# SH6_-_SCIENCECONTROLS.net
KiCad netlist of a schematic drawn in Altium Designer
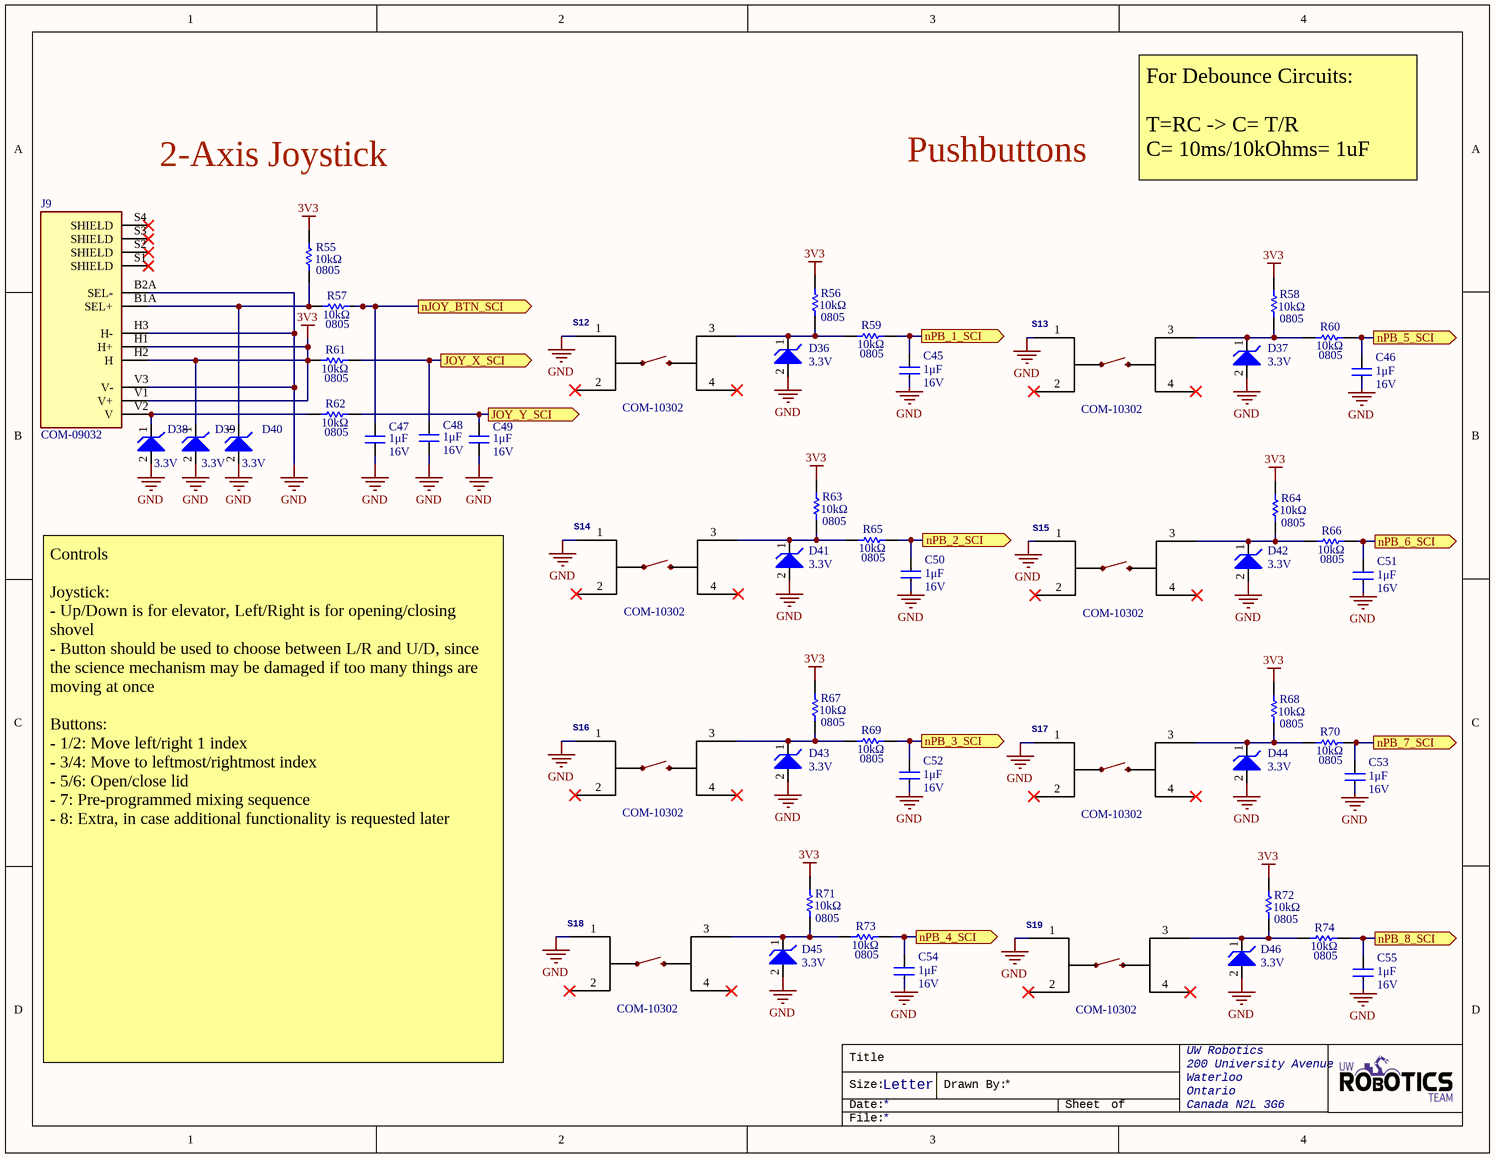
[diagram p0: SH6 - SCIENCECONTROLS.SchDoc]

(export (version "E")
  (design (tool "Eeschema 10.0.6"))
  (components
    (comp (ref "C45")
      (value "1μF")
      (footprint "CAP2012")
      (description "CAP CER 1UF 16V X7R 0805")
      (fields
        (field (name "TOLERANCE") "10%")
        (field (name "VOLTAGE RATING") "16V")
        (field (name "Comment") "CAP_1uF_16V_0805")
      )
      (libsource (lib "UWRT_Schematic_Library_2020") (part "CAP_1uF_16V_0805"))
    )
    (comp (ref "C46")
      (value "1μF")
      (footprint "CAP2012")
      (description "CAP CER 1UF 16V X7R 0805")
      (fields
        (field (name "TOLERANCE") "10%")
        (field (name "VOLTAGE RATING") "16V")
        (field (name "Comment") "CAP_1uF_16V_0805")
      )
      (libsource (lib "UWRT_Schematic_Library_2020") (part "CAP_1uF_16V_0805"))
    )
    (comp (ref "C47")
      (value "1μF")
      (footprint "CAP2012")
      (description "CAP CER 1UF 16V X7R 0805")
      (fields
        (field (name "TOLERANCE") "10%")
        (field (name "VOLTAGE RATING") "16V")
        (field (name "Comment") "CAP_1uF_16V_0805")
      )
      (libsource (lib "UWRT_Schematic_Library_2020") (part "CAP_1uF_16V_0805"))
    )
    (comp (ref "C48")
      (value "1μF")
      (footprint "CAP2012")
      (description "CAP CER 1UF 16V X7R 0805")
      (fields
        (field (name "TOLERANCE") "10%")
        (field (name "VOLTAGE RATING") "16V")
        (field (name "Comment") "CAP_1uF_16V_0805")
      )
      (libsource (lib "UWRT_Schematic_Library_2020") (part "CAP_1uF_16V_0805"))
    )
    (comp (ref "C49")
      (value "1μF")
      (footprint "CAP2012")
      (description "CAP CER 1UF 16V X7R 0805")
      (fields
        (field (name "TOLERANCE") "10%")
        (field (name "VOLTAGE RATING") "16V")
        (field (name "Comment") "CAP_1uF_16V_0805")
      )
      (libsource (lib "UWRT_Schematic_Library_2020") (part "CAP_1uF_16V_0805"))
    )
    (comp (ref "C50")
      (value "1μF")
      (footprint "CAP2012")
      (description "CAP CER 1UF 16V X7R 0805")
      (fields
        (field (name "TOLERANCE") "10%")
        (field (name "VOLTAGE RATING") "16V")
        (field (name "Comment") "CAP_1uF_16V_0805")
      )
      (libsource (lib "UWRT_Schematic_Library_2020") (part "CAP_1uF_16V_0805"))
    )
    (comp (ref "C51")
      (value "1μF")
      (footprint "CAP2012")
      (description "CAP CER 1UF 16V X7R 0805")
      (fields
        (field (name "TOLERANCE") "10%")
        (field (name "VOLTAGE RATING") "16V")
        (field (name "Comment") "CAP_1uF_16V_0805")
      )
      (libsource (lib "UWRT_Schematic_Library_2020") (part "CAP_1uF_16V_0805"))
    )
    (comp (ref "C52")
      (value "1μF")
      (footprint "CAP2012")
      (description "CAP CER 1UF 16V X7R 0805")
      (fields
        (field (name "TOLERANCE") "10%")
        (field (name "VOLTAGE RATING") "16V")
        (field (name "Comment") "CAP_1uF_16V_0805")
      )
      (libsource (lib "UWRT_Schematic_Library_2020") (part "CAP_1uF_16V_0805"))
    )
    (comp (ref "C53")
      (value "1μF")
      (footprint "CAP2012")
      (description "CAP CER 1UF 16V X7R 0805")
      (fields
        (field (name "TOLERANCE") "10%")
        (field (name "VOLTAGE RATING") "16V")
        (field (name "Comment") "CAP_1uF_16V_0805")
      )
      (libsource (lib "UWRT_Schematic_Library_2020") (part "CAP_1uF_16V_0805"))
    )
    (comp (ref "C54")
      (value "1μF")
      (footprint "CAP2012")
      (description "CAP CER 1UF 16V X7R 0805")
      (fields
        (field (name "TOLERANCE") "10%")
        (field (name "VOLTAGE RATING") "16V")
        (field (name "Comment") "CAP_1uF_16V_0805")
      )
      (libsource (lib "UWRT_Schematic_Library_2020") (part "CAP_1uF_16V_0805"))
    )
    (comp (ref "C55")
      (value "1μF")
      (footprint "CAP2012")
      (description "CAP CER 1UF 16V X7R 0805")
      (fields
        (field (name "TOLERANCE") "10%")
        (field (name "VOLTAGE RATING") "16V")
        (field (name "Comment") "CAP_1uF_16V_0805")
      )
      (libsource (lib "UWRT_Schematic_Library_2020") (part "CAP_1uF_16V_0805"))
    )
    (comp (ref "D36")
      (value "TVS_DIODE_UNIDIR_3.3V")
      (footprint "SOD523")
      (description "TVS DIODE 3.3V 14.1V SOD523. Used to protect each connector input line going into the MCU.")
      (fields (field (name "REVERSE STANDOFF VOLTAGE") "3.3V"))
      (libsource (lib "UWRT_Schematic_Library_2020") (part "TVS_DIODE_UNIDIR_3.3V"))
    )
    (comp (ref "D37")
      (value "TVS_DIODE_UNIDIR_3.3V")
      (footprint "SOD523")
      (description "TVS DIODE 3.3V 14.1V SOD523. Used to protect each connector input line going into the MCU.")
      (fields (field (name "REVERSE STANDOFF VOLTAGE") "3.3V"))
      (libsource (lib "UWRT_Schematic_Library_2020") (part "TVS_DIODE_UNIDIR_3.3V"))
    )
    (comp (ref "D38")
      (value "TVS_DIODE_UNIDIR_3.3V")
      (footprint "SOD523")
      (description "TVS DIODE 3.3V 14.1V SOD523. Used to protect each connector input line going into the MCU.")
      (fields (field (name "REVERSE STANDOFF VOLTAGE") "3.3V"))
      (libsource (lib "UWRT_Schematic_Library_2020") (part "TVS_DIODE_UNIDIR_3.3V"))
    )
    (comp (ref "D39")
      (value "TVS_DIODE_UNIDIR_3.3V")
      (footprint "SOD523")
      (description "TVS DIODE 3.3V 14.1V SOD523. Used to protect each connector input line going into the MCU.")
      (fields (field (name "REVERSE STANDOFF VOLTAGE") "3.3V"))
      (libsource (lib "UWRT_Schematic_Library_2020") (part "TVS_DIODE_UNIDIR_3.3V"))
    )
    (comp (ref "D40")
      (value "TVS_DIODE_UNIDIR_3.3V")
      (footprint "SOD523")
      (description "TVS DIODE 3.3V 14.1V SOD523. Used to protect each connector input line going into the MCU.")
      (fields (field (name "REVERSE STANDOFF VOLTAGE") "3.3V"))
      (libsource (lib "UWRT_Schematic_Library_2020") (part "TVS_DIODE_UNIDIR_3.3V"))
    )
    (comp (ref "D41")
      (value "TVS_DIODE_UNIDIR_3.3V")
      (footprint "SOD523")
      (description "TVS DIODE 3.3V 14.1V SOD523. Used to protect each connector input line going into the MCU.")
      (fields (field (name "REVERSE STANDOFF VOLTAGE") "3.3V"))
      (libsource (lib "UWRT_Schematic_Library_2020") (part "TVS_DIODE_UNIDIR_3.3V"))
    )
    (comp (ref "D42")
      (value "TVS_DIODE_UNIDIR_3.3V")
      (footprint "SOD523")
      (description "TVS DIODE 3.3V 14.1V SOD523. Used to protect each connector input line going into the MCU.")
      (fields (field (name "REVERSE STANDOFF VOLTAGE") "3.3V"))
      (libsource (lib "UWRT_Schematic_Library_2020") (part "TVS_DIODE_UNIDIR_3.3V"))
    )
    (comp (ref "D43")
      (value "TVS_DIODE_UNIDIR_3.3V")
      (footprint "SOD523")
      (description "TVS DIODE 3.3V 14.1V SOD523. Used to protect each connector input line going into the MCU.")
      (fields (field (name "REVERSE STANDOFF VOLTAGE") "3.3V"))
      (libsource (lib "UWRT_Schematic_Library_2020") (part "TVS_DIODE_UNIDIR_3.3V"))
    )
    (comp (ref "D44")
      (value "TVS_DIODE_UNIDIR_3.3V")
      (footprint "SOD523")
      (description "TVS DIODE 3.3V 14.1V SOD523. Used to protect each connector input line going into the MCU.")
      (fields (field (name "REVERSE STANDOFF VOLTAGE") "3.3V"))
      (libsource (lib "UWRT_Schematic_Library_2020") (part "TVS_DIODE_UNIDIR_3.3V"))
    )
    (comp (ref "D45")
      (value "TVS_DIODE_UNIDIR_3.3V")
      (footprint "SOD523")
      (description "TVS DIODE 3.3V 14.1V SOD523. Used to protect each connector input line going into the MCU.")
      (fields (field (name "REVERSE STANDOFF VOLTAGE") "3.3V"))
      (libsource (lib "UWRT_Schematic_Library_2020") (part "TVS_DIODE_UNIDIR_3.3V"))
    )
    (comp (ref "D46")
      (value "TVS_DIODE_UNIDIR_3.3V")
      (footprint "SOD523")
      (description "TVS DIODE 3.3V 14.1V SOD523. Used to protect each connector input line going into the MCU.")
      (fields (field (name "REVERSE STANDOFF VOLTAGE") "3.3V"))
      (libsource (lib "UWRT_Schematic_Library_2020") (part "TVS_DIODE_UNIDIR_3.3V"))
    )
    (comp (ref "J9")
      (value "2_AXIS_JOYSTICK")
      (footprint "2_AXIS_JOYSTICK")
      (description "JOYSTICK 10K OHM 2 AXIS TH")
      (fields (field (name "MANUFACTURER PART NUMBER 1") "COM-09032"))
      (libsource (lib "UWRT_Schematic_Library_2020") (part "2_AXIS_JOYSTICK"))
    )
    (comp (ref "R55")
      (value "10kΩ")
      (footprint "RESC0805")
      (description "RES 10K OHM 5% 1/8W 0805")
      (fields (field (name "CASE CODE (IMPERIAL)") "0805") (field (name "Comment") "RES_10kΩ_0805_5%"))
      (libsource (lib "UWRT_Schematic_Library_2020") (part "RES_10kΩ_0805_5%"))
    )
    (comp (ref "R56")
      (value "10kΩ")
      (footprint "RESC0805")
      (description "RES 10K OHM 5% 1/8W 0805")
      (fields (field (name "CASE CODE (IMPERIAL)") "0805") (field (name "Comment") "RES_10kΩ_0805_5%"))
      (libsource (lib "UWRT_Schematic_Library_2020") (part "RES_10kΩ_0805_5%"))
    )
    (comp (ref "R57")
      (value "10kΩ")
      (footprint "RESC0805")
      (description "RES 10K OHM 5% 1/8W 0805")
      (fields (field (name "CASE CODE (IMPERIAL)") "0805") (field (name "Comment") "RES_10kΩ_0805_5%"))
      (libsource (lib "UWRT_Schematic_Library_2020") (part "RES_10kΩ_0805_5%"))
    )
    (comp (ref "R58")
      (value "10kΩ")
      (footprint "RESC0805")
      (description "RES 10K OHM 5% 1/8W 0805")
      (fields (field (name "CASE CODE (IMPERIAL)") "0805") (field (name "Comment") "RES_10kΩ_0805_5%"))
      (libsource (lib "UWRT_Schematic_Library_2020") (part "RES_10kΩ_0805_5%"))
    )
    (comp (ref "R59")
      (value "10kΩ")
      (footprint "RESC0805")
      (description "RES 10K OHM 5% 1/8W 0805")
      (fields (field (name "CASE CODE (IMPERIAL)") "0805") (field (name "Comment") "RES_10kΩ_0805_5%"))
      (libsource (lib "UWRT_Schematic_Library_2020") (part "RES_10kΩ_0805_5%"))
    )
    (comp (ref "R60")
      (value "10kΩ")
      (footprint "RESC0805")
      (description "RES 10K OHM 5% 1/8W 0805")
      (fields (field (name "CASE CODE (IMPERIAL)") "0805") (field (name "Comment") "RES_10kΩ_0805_5%"))
      (libsource (lib "UWRT_Schematic_Library_2020") (part "RES_10kΩ_0805_5%"))
    )
    (comp (ref "R61")
      (value "10kΩ")
      (footprint "RESC0805")
      (description "RES 10K OHM 5% 1/8W 0805")
      (fields (field (name "CASE CODE (IMPERIAL)") "0805") (field (name "Comment") "RES_10kΩ_0805_5%"))
      (libsource (lib "UWRT_Schematic_Library_2020") (part "RES_10kΩ_0805_5%"))
    )
    (comp (ref "R62")
      (value "10kΩ")
      (footprint "RESC0805")
      (description "RES 10K OHM 5% 1/8W 0805")
      (fields (field (name "CASE CODE (IMPERIAL)") "0805") (field (name "Comment") "RES_10kΩ_0805_5%"))
      (libsource (lib "UWRT_Schematic_Library_2020") (part "RES_10kΩ_0805_5%"))
    )
    (comp (ref "R63")
      (value "10kΩ")
      (footprint "RESC0805")
      (description "RES 10K OHM 5% 1/8W 0805")
      (fields (field (name "CASE CODE (IMPERIAL)") "0805") (field (name "Comment") "RES_10kΩ_0805_5%"))
      (libsource (lib "UWRT_Schematic_Library_2020") (part "RES_10kΩ_0805_5%"))
    )
    (comp (ref "R64")
      (value "10kΩ")
      (footprint "RESC0805")
      (description "RES 10K OHM 5% 1/8W 0805")
      (fields (field (name "CASE CODE (IMPERIAL)") "0805") (field (name "Comment") "RES_10kΩ_0805_5%"))
      (libsource (lib "UWRT_Schematic_Library_2020") (part "RES_10kΩ_0805_5%"))
    )
    (comp (ref "R65")
      (value "10kΩ")
      (footprint "RESC0805")
      (description "RES 10K OHM 5% 1/8W 0805")
      (fields (field (name "CASE CODE (IMPERIAL)") "0805") (field (name "Comment") "RES_10kΩ_0805_5%"))
      (libsource (lib "UWRT_Schematic_Library_2020") (part "RES_10kΩ_0805_5%"))
    )
    (comp (ref "R66")
      (value "10kΩ")
      (footprint "RESC0805")
      (description "RES 10K OHM 5% 1/8W 0805")
      (fields (field (name "CASE CODE (IMPERIAL)") "0805") (field (name "Comment") "RES_10kΩ_0805_5%"))
      (libsource (lib "UWRT_Schematic_Library_2020") (part "RES_10kΩ_0805_5%"))
    )
    (comp (ref "R67")
      (value "10kΩ")
      (footprint "RESC0805")
      (description "RES 10K OHM 5% 1/8W 0805")
      (fields (field (name "CASE CODE (IMPERIAL)") "0805") (field (name "Comment") "RES_10kΩ_0805_5%"))
      (libsource (lib "UWRT_Schematic_Library_2020") (part "RES_10kΩ_0805_5%"))
    )
    (comp (ref "R68")
      (value "10kΩ")
      (footprint "RESC0805")
      (description "RES 10K OHM 5% 1/8W 0805")
      (fields (field (name "CASE CODE (IMPERIAL)") "0805") (field (name "Comment") "RES_10kΩ_0805_5%"))
      (libsource (lib "UWRT_Schematic_Library_2020") (part "RES_10kΩ_0805_5%"))
    )
    (comp (ref "R69")
      (value "10kΩ")
      (footprint "RESC0805")
      (description "RES 10K OHM 5% 1/8W 0805")
      (fields (field (name "CASE CODE (IMPERIAL)") "0805") (field (name "Comment") "RES_10kΩ_0805_5%"))
      (libsource (lib "UWRT_Schematic_Library_2020") (part "RES_10kΩ_0805_5%"))
    )
    (comp (ref "R70")
      (value "10kΩ")
      (footprint "RESC0805")
      (description "RES 10K OHM 5% 1/8W 0805")
      (fields (field (name "CASE CODE (IMPERIAL)") "0805") (field (name "Comment") "RES_10kΩ_0805_5%"))
      (libsource (lib "UWRT_Schematic_Library_2020") (part "RES_10kΩ_0805_5%"))
    )
    (comp (ref "R71")
      (value "10kΩ")
      (footprint "RESC0805")
      (description "RES 10K OHM 5% 1/8W 0805")
      (fields (field (name "CASE CODE (IMPERIAL)") "0805") (field (name "Comment") "RES_10kΩ_0805_5%"))
      (libsource (lib "UWRT_Schematic_Library_2020") (part "RES_10kΩ_0805_5%"))
    )
    (comp (ref "R72")
      (value "10kΩ")
      (footprint "RESC0805")
      (description "RES 10K OHM 5% 1/8W 0805")
      (fields (field (name "CASE CODE (IMPERIAL)") "0805") (field (name "Comment") "RES_10kΩ_0805_5%"))
      (libsource (lib "UWRT_Schematic_Library_2020") (part "RES_10kΩ_0805_5%"))
    )
    (comp (ref "R73")
      (value "10kΩ")
      (footprint "RESC0805")
      (description "RES 10K OHM 5% 1/8W 0805")
      (fields (field (name "CASE CODE (IMPERIAL)") "0805") (field (name "Comment") "RES_10kΩ_0805_5%"))
      (libsource (lib "UWRT_Schematic_Library_2020") (part "RES_10kΩ_0805_5%"))
    )
    (comp (ref "R74")
      (value "10kΩ")
      (footprint "RESC0805")
      (description "RES 10K OHM 5% 1/8W 0805")
      (fields (field (name "CASE CODE (IMPERIAL)") "0805") (field (name "Comment") "RES_10kΩ_0805_5%"))
      (libsource (lib "UWRT_Schematic_Library_2020") (part "RES_10kΩ_0805_5%"))
    )
    (comp (ref "S12")
      (value "Pushbutton")
      (footprint "TACTILE_SWITCH_PTH_12MM")
      (description "TACTILE MOMENTARY PUSHBUTTON SPST")
      (fields (field (name "MANUFACTURER PART NUMBER 1") "COM-10302"))
      (libsource (lib "UWRT_Schematic_Library_2020") (part "MOMENTARY_SWITCH_TH"))
    )
    (comp (ref "S13")
      (value "Pushbutton")
      (footprint "TACTILE_SWITCH_PTH_12MM")
      (description "TACTILE MOMENTARY PUSHBUTTON SPST")
      (fields (field (name "MANUFACTURER PART NUMBER 1") "COM-10302"))
      (libsource (lib "UWRT_Schematic_Library_2020") (part "MOMENTARY_SWITCH_TH"))
    )
    (comp (ref "S14")
      (value "Pushbutton")
      (footprint "TACTILE_SWITCH_PTH_12MM")
      (description "TACTILE MOMENTARY PUSHBUTTON SPST")
      (fields (field (name "MANUFACTURER PART NUMBER 1") "COM-10302"))
      (libsource (lib "UWRT_Schematic_Library_2020") (part "MOMENTARY_SWITCH_TH"))
    )
    (comp (ref "S15")
      (value "Pushbutton")
      (footprint "TACTILE_SWITCH_PTH_12MM")
      (description "TACTILE MOMENTARY PUSHBUTTON SPST")
      (fields (field (name "MANUFACTURER PART NUMBER 1") "COM-10302"))
      (libsource (lib "UWRT_Schematic_Library_2020") (part "MOMENTARY_SWITCH_TH"))
    )
    (comp (ref "S16")
      (value "Pushbutton")
      (footprint "TACTILE_SWITCH_PTH_12MM")
      (description "TACTILE MOMENTARY PUSHBUTTON SPST")
      (fields (field (name "MANUFACTURER PART NUMBER 1") "COM-10302"))
      (libsource (lib "UWRT_Schematic_Library_2020") (part "MOMENTARY_SWITCH_TH"))
    )
    (comp (ref "S17")
      (value "Pushbutton")
      (footprint "TACTILE_SWITCH_PTH_12MM")
      (description "TACTILE MOMENTARY PUSHBUTTON SPST")
      (fields (field (name "MANUFACTURER PART NUMBER 1") "COM-10302"))
      (libsource (lib "UWRT_Schematic_Library_2020") (part "MOMENTARY_SWITCH_TH"))
    )
    (comp (ref "S18")
      (value "Pushbutton")
      (footprint "TACTILE_SWITCH_PTH_12MM")
      (description "TACTILE MOMENTARY PUSHBUTTON SPST")
      (fields (field (name "MANUFACTURER PART NUMBER 1") "COM-10302"))
      (libsource (lib "UWRT_Schematic_Library_2020") (part "MOMENTARY_SWITCH_TH"))
    )
    (comp (ref "S19")
      (value "Pushbutton")
      (footprint "TACTILE_SWITCH_PTH_12MM")
      (description "TACTILE MOMENTARY PUSHBUTTON SPST")
      (fields (field (name "MANUFACTURER PART NUMBER 1") "COM-10302"))
      (libsource (lib "UWRT_Schematic_Library_2020") (part "MOMENTARY_SWITCH_TH"))
    )
  )
  (nets
    (net (code "1") (name "/JOY_X_SCI") (class "Default")
      (node (ref "C48") (pin "2") (pinfunction "2_2") (pintype "passive"))
      (node (ref "R61") (pin "2") (pinfunction "2_2") (pintype "passive"))
    )
    (net (code "2") (name "/JOY_Y_SCI") (class "Default")
      (node (ref "C49") (pin "2") (pinfunction "2_2") (pintype "passive"))
      (node (ref "R62") (pin "2") (pinfunction "2_2") (pintype "passive"))
    )
    (net (code "3") (name "/nJOY_BTN_SCI") (class "Default")
      (node (ref "C47") (pin "2") (pinfunction "2_2") (pintype "passive"))
      (node (ref "R57") (pin "2") (pinfunction "2_2") (pintype "passive"))
    )
    (net (code "4") (name "/nPB_1_SCI") (class "Default")
      (node (ref "C45") (pin "2") (pinfunction "2_2") (pintype "passive"))
      (node (ref "R59") (pin "2") (pinfunction "2_2") (pintype "passive"))
    )
    (net (code "5") (name "/nPB_2_SCI") (class "Default")
      (node (ref "C50") (pin "2") (pinfunction "2_2") (pintype "passive"))
      (node (ref "R65") (pin "2") (pinfunction "2_2") (pintype "passive"))
    )
    (net (code "6") (name "/nPB_3_SCI") (class "Default")
      (node (ref "C52") (pin "2") (pinfunction "2_2") (pintype "passive"))
      (node (ref "R69") (pin "2") (pinfunction "2_2") (pintype "passive"))
    )
    (net (code "7") (name "/nPB_4_SCI") (class "Default")
      (node (ref "C54") (pin "2") (pinfunction "2_2") (pintype "passive"))
      (node (ref "R73") (pin "2") (pinfunction "2_2") (pintype "passive"))
    )
    (net (code "8") (name "/nPB_5_SCI") (class "Default")
      (node (ref "C46") (pin "2") (pinfunction "2_2") (pintype "passive"))
      (node (ref "R60") (pin "2") (pinfunction "2_2") (pintype "passive"))
    )
    (net (code "9") (name "/nPB_6_SCI") (class "Default")
      (node (ref "C51") (pin "2") (pinfunction "2_2") (pintype "passive"))
      (node (ref "R66") (pin "2") (pinfunction "2_2") (pintype "passive"))
    )
    (net (code "10") (name "/nPB_7_SCI") (class "Default")
      (node (ref "C53") (pin "2") (pinfunction "2_2") (pintype "passive"))
      (node (ref "R70") (pin "2") (pinfunction "2_2") (pintype "passive"))
    )
    (net (code "11") (name "/nPB_8_SCI") (class "Default")
      (node (ref "C55") (pin "2") (pinfunction "2_2") (pintype "passive"))
      (node (ref "R74") (pin "2") (pinfunction "2_2") (pintype "passive"))
    )
    (net (code "12") (name "3V3") (class "Default")
      (node (ref "D39") (pin "1") (pinfunction "1_1") (pintype "passive"))
      (node (ref "J9") (pin "H1") (pinfunction "H+_H1") (pintype "passive"))
      (node (ref "J9") (pin "H2") (pinfunction "H_H2") (pintype "passive"))
      (node (ref "J9") (pin "V1") (pinfunction "V+_V1") (pintype "passive"))
      (node (ref "R55") (pin "1") (pinfunction "1_1") (pintype "passive"))
      (node (ref "R56") (pin "1") (pinfunction "1_1") (pintype "passive"))
      (node (ref "R58") (pin "1") (pinfunction "1_1") (pintype "passive"))
      (node (ref "R61") (pin "1") (pinfunction "1_1") (pintype "passive"))
      (node (ref "R63") (pin "1") (pinfunction "1_1") (pintype "passive"))
      (node (ref "R64") (pin "1") (pinfunction "1_1") (pintype "passive"))
      (node (ref "R67") (pin "1") (pinfunction "1_1") (pintype "passive"))
      (node (ref "R68") (pin "1") (pinfunction "1_1") (pintype "passive"))
      (node (ref "R71") (pin "1") (pinfunction "1_1") (pintype "passive"))
      (node (ref "R72") (pin "1") (pinfunction "1_1") (pintype "passive"))
    )
    (net (code "13") (name "GND") (class "Default")
      (node (ref "C45") (pin "1") (pinfunction "1_1") (pintype "passive"))
      (node (ref "C46") (pin "1") (pinfunction "1_1") (pintype "passive"))
      (node (ref "C47") (pin "1") (pinfunction "1_1") (pintype "passive"))
      (node (ref "C48") (pin "1") (pinfunction "1_1") (pintype "passive"))
      (node (ref "C49") (pin "1") (pinfunction "1_1") (pintype "passive"))
      (node (ref "C50") (pin "1") (pinfunction "1_1") (pintype "passive"))
      (node (ref "C51") (pin "1") (pinfunction "1_1") (pintype "passive"))
      (node (ref "C52") (pin "1") (pinfunction "1_1") (pintype "passive"))
      (node (ref "C53") (pin "1") (pinfunction "1_1") (pintype "passive"))
      (node (ref "C54") (pin "1") (pinfunction "1_1") (pintype "passive"))
      (node (ref "C55") (pin "1") (pinfunction "1_1") (pintype "passive"))
      (node (ref "D36") (pin "2") (pinfunction "2_2") (pintype "passive"))
      (node (ref "D37") (pin "2") (pinfunction "2_2") (pintype "passive"))
      (node (ref "D38") (pin "2") (pinfunction "2_2") (pintype "passive"))
      (node (ref "D39") (pin "2") (pinfunction "2_2") (pintype "passive"))
      (node (ref "D40") (pin "2") (pinfunction "2_2") (pintype "passive"))
      (node (ref "D41") (pin "2") (pinfunction "2_2") (pintype "passive"))
      (node (ref "D42") (pin "2") (pinfunction "2_2") (pintype "passive"))
      (node (ref "D43") (pin "2") (pinfunction "2_2") (pintype "passive"))
      (node (ref "D44") (pin "2") (pinfunction "2_2") (pintype "passive"))
      (node (ref "D45") (pin "2") (pinfunction "2_2") (pintype "passive"))
      (node (ref "D46") (pin "2") (pinfunction "2_2") (pintype "passive"))
      (node (ref "J9") (pin "B2A") (pinfunction "SEL-_B2A") (pintype "passive"))
      (node (ref "J9") (pin "H3") (pinfunction "H-_H3") (pintype "passive"))
      (node (ref "J9") (pin "V3") (pinfunction "V-_V3") (pintype "passive"))
      (node (ref "S12") (pin "1") (pinfunction "1_1") (pintype "passive"))
      (node (ref "S13") (pin "1") (pinfunction "1_1") (pintype "passive"))
      (node (ref "S14") (pin "1") (pinfunction "1_1") (pintype "passive"))
      (node (ref "S15") (pin "1") (pinfunction "1_1") (pintype "passive"))
      (node (ref "S16") (pin "1") (pinfunction "1_1") (pintype "passive"))
      (node (ref "S17") (pin "1") (pinfunction "1_1") (pintype "passive"))
      (node (ref "S18") (pin "1") (pinfunction "1_1") (pintype "passive"))
      (node (ref "S19") (pin "1") (pinfunction "1_1") (pintype "passive"))
    )
    (net (code "14") (name "Net-(D36-Pad1)") (class "Default")
      (node (ref "D36") (pin "1") (pinfunction "1_1") (pintype "passive"))
      (node (ref "R56") (pin "2") (pinfunction "2_2") (pintype "passive"))
      (node (ref "R59") (pin "1") (pinfunction "1_1") (pintype "passive"))
      (node (ref "S12") (pin "3") (pinfunction "3_3") (pintype "passive"))
    )
    (net (code "15") (name "Net-(D37-Pad1)") (class "Default")
      (node (ref "D37") (pin "1") (pinfunction "1_1") (pintype "passive"))
      (node (ref "R58") (pin "2") (pinfunction "2_2") (pintype "passive"))
      (node (ref "R60") (pin "1") (pinfunction "1_1") (pintype "passive"))
      (node (ref "S13") (pin "3") (pinfunction "3_3") (pintype "passive"))
    )
    (net (code "16") (name "Net-(D41-Pad1)") (class "Default")
      (node (ref "D41") (pin "1") (pinfunction "1_1") (pintype "passive"))
      (node (ref "R63") (pin "2") (pinfunction "2_2") (pintype "passive"))
      (node (ref "R65") (pin "1") (pinfunction "1_1") (pintype "passive"))
      (node (ref "S14") (pin "3") (pinfunction "3_3") (pintype "passive"))
    )
    (net (code "17") (name "Net-(D42-Pad1)") (class "Default")
      (node (ref "D42") (pin "1") (pinfunction "1_1") (pintype "passive"))
      (node (ref "R64") (pin "2") (pinfunction "2_2") (pintype "passive"))
      (node (ref "R66") (pin "1") (pinfunction "1_1") (pintype "passive"))
      (node (ref "S15") (pin "3") (pinfunction "3_3") (pintype "passive"))
    )
    (net (code "18") (name "Net-(D43-Pad1)") (class "Default")
      (node (ref "D43") (pin "1") (pinfunction "1_1") (pintype "passive"))
      (node (ref "R67") (pin "2") (pinfunction "2_2") (pintype "passive"))
      (node (ref "R69") (pin "1") (pinfunction "1_1") (pintype "passive"))
      (node (ref "S16") (pin "3") (pinfunction "3_3") (pintype "passive"))
    )
    (net (code "19") (name "Net-(D44-Pad1)") (class "Default")
      (node (ref "D44") (pin "1") (pinfunction "1_1") (pintype "passive"))
      (node (ref "R68") (pin "2") (pinfunction "2_2") (pintype "passive"))
      (node (ref "R70") (pin "1") (pinfunction "1_1") (pintype "passive"))
      (node (ref "S17") (pin "3") (pinfunction "3_3") (pintype "passive"))
    )
    (net (code "20") (name "Net-(D45-Pad1)") (class "Default")
      (node (ref "D45") (pin "1") (pinfunction "1_1") (pintype "passive"))
      (node (ref "R71") (pin "2") (pinfunction "2_2") (pintype "passive"))
      (node (ref "R73") (pin "1") (pinfunction "1_1") (pintype "passive"))
      (node (ref "S18") (pin "3") (pinfunction "3_3") (pintype "passive"))
    )
    (net (code "21") (name "Net-(D46-Pad1)") (class "Default")
      (node (ref "D46") (pin "1") (pinfunction "1_1") (pintype "passive"))
      (node (ref "R72") (pin "2") (pinfunction "2_2") (pintype "passive"))
      (node (ref "R74") (pin "1") (pinfunction "1_1") (pintype "passive"))
      (node (ref "S19") (pin "3") (pinfunction "3_3") (pintype "passive"))
    )
    (net (code "22") (name "Net-(J9-SEL+)") (class "Default")
      (node (ref "D40") (pin "1") (pinfunction "1_1") (pintype "passive"))
      (node (ref "J9") (pin "B1A") (pinfunction "SEL+_B1A") (pintype "passive"))
      (node (ref "R55") (pin "2") (pinfunction "2_2") (pintype "passive"))
      (node (ref "R57") (pin "1") (pinfunction "1_1") (pintype "passive"))
    )
    (net (code "23") (name "Net-(J9-V)") (class "Default")
      (node (ref "D38") (pin "1") (pinfunction "1_1") (pintype "passive"))
      (node (ref "J9") (pin "V2") (pinfunction "V_V2") (pintype "passive"))
      (node (ref "R62") (pin "1") (pinfunction "1_1") (pintype "passive"))
    )
    (net (code "24") (name "unconnected-(J9-SHIELD-PadS1)") (class "Default")
      (node (ref "J9") (pin "S1") (pinfunction "SHIELD_S1") (pintype "passive+no_connect"))
    )
    (net (code "25") (name "unconnected-(J9-SHIELD-PadS2)") (class "Default")
      (node (ref "J9") (pin "S2") (pinfunction "SHIELD_S2") (pintype "passive+no_connect"))
    )
    (net (code "26") (name "unconnected-(J9-SHIELD-PadS3)") (class "Default")
      (node (ref "J9") (pin "S3") (pinfunction "SHIELD_S3") (pintype "passive+no_connect"))
    )
    (net (code "27") (name "unconnected-(J9-SHIELD-PadS4)") (class "Default")
      (node (ref "J9") (pin "S4") (pinfunction "SHIELD_S4") (pintype "passive+no_connect"))
    )
    (net (code "28") (name "unconnected-(S12-Pad2)") (class "Default")
      (node (ref "S12") (pin "2") (pinfunction "2_2") (pintype "passive+no_connect"))
    )
    (net (code "29") (name "unconnected-(S12-Pad4)") (class "Default")
      (node (ref "S12") (pin "4") (pinfunction "4_4") (pintype "passive+no_connect"))
    )
    (net (code "30") (name "unconnected-(S13-Pad2)") (class "Default")
      (node (ref "S13") (pin "2") (pinfunction "2_2") (pintype "passive+no_connect"))
    )
    (net (code "31") (name "unconnected-(S13-Pad4)") (class "Default")
      (node (ref "S13") (pin "4") (pinfunction "4_4") (pintype "passive+no_connect"))
    )
    (net (code "32") (name "unconnected-(S14-Pad2)") (class "Default")
      (node (ref "S14") (pin "2") (pinfunction "2_2") (pintype "passive+no_connect"))
    )
    (net (code "33") (name "unconnected-(S14-Pad4)") (class "Default")
      (node (ref "S14") (pin "4") (pinfunction "4_4") (pintype "passive+no_connect"))
    )
    (net (code "34") (name "unconnected-(S15-Pad2)") (class "Default")
      (node (ref "S15") (pin "2") (pinfunction "2_2") (pintype "passive+no_connect"))
    )
    (net (code "35") (name "unconnected-(S15-Pad4)") (class "Default")
      (node (ref "S15") (pin "4") (pinfunction "4_4") (pintype "passive+no_connect"))
    )
    (net (code "36") (name "unconnected-(S16-Pad2)") (class "Default")
      (node (ref "S16") (pin "2") (pinfunction "2_2") (pintype "passive+no_connect"))
    )
    (net (code "37") (name "unconnected-(S16-Pad4)") (class "Default")
      (node (ref "S16") (pin "4") (pinfunction "4_4") (pintype "passive+no_connect"))
    )
    (net (code "38") (name "unconnected-(S17-Pad2)") (class "Default")
      (node (ref "S17") (pin "2") (pinfunction "2_2") (pintype "passive+no_connect"))
    )
    (net (code "39") (name "unconnected-(S17-Pad4)") (class "Default")
      (node (ref "S17") (pin "4") (pinfunction "4_4") (pintype "passive+no_connect"))
    )
    (net (code "40") (name "unconnected-(S18-Pad2)") (class "Default")
      (node (ref "S18") (pin "2") (pinfunction "2_2") (pintype "passive+no_connect"))
    )
    (net (code "41") (name "unconnected-(S18-Pad4)") (class "Default")
      (node (ref "S18") (pin "4") (pinfunction "4_4") (pintype "passive+no_connect"))
    )
    (net (code "42") (name "unconnected-(S19-Pad2)") (class "Default")
      (node (ref "S19") (pin "2") (pinfunction "2_2") (pintype "passive+no_connect"))
    )
    (net (code "43") (name "unconnected-(S19-Pad4)") (class "Default")
      (node (ref "S19") (pin "4") (pinfunction "4_4") (pintype "passive+no_connect"))
    )
  )
)
